# SOS_sender.net
KiCad netlist of a schematic drawn in EasyEDA
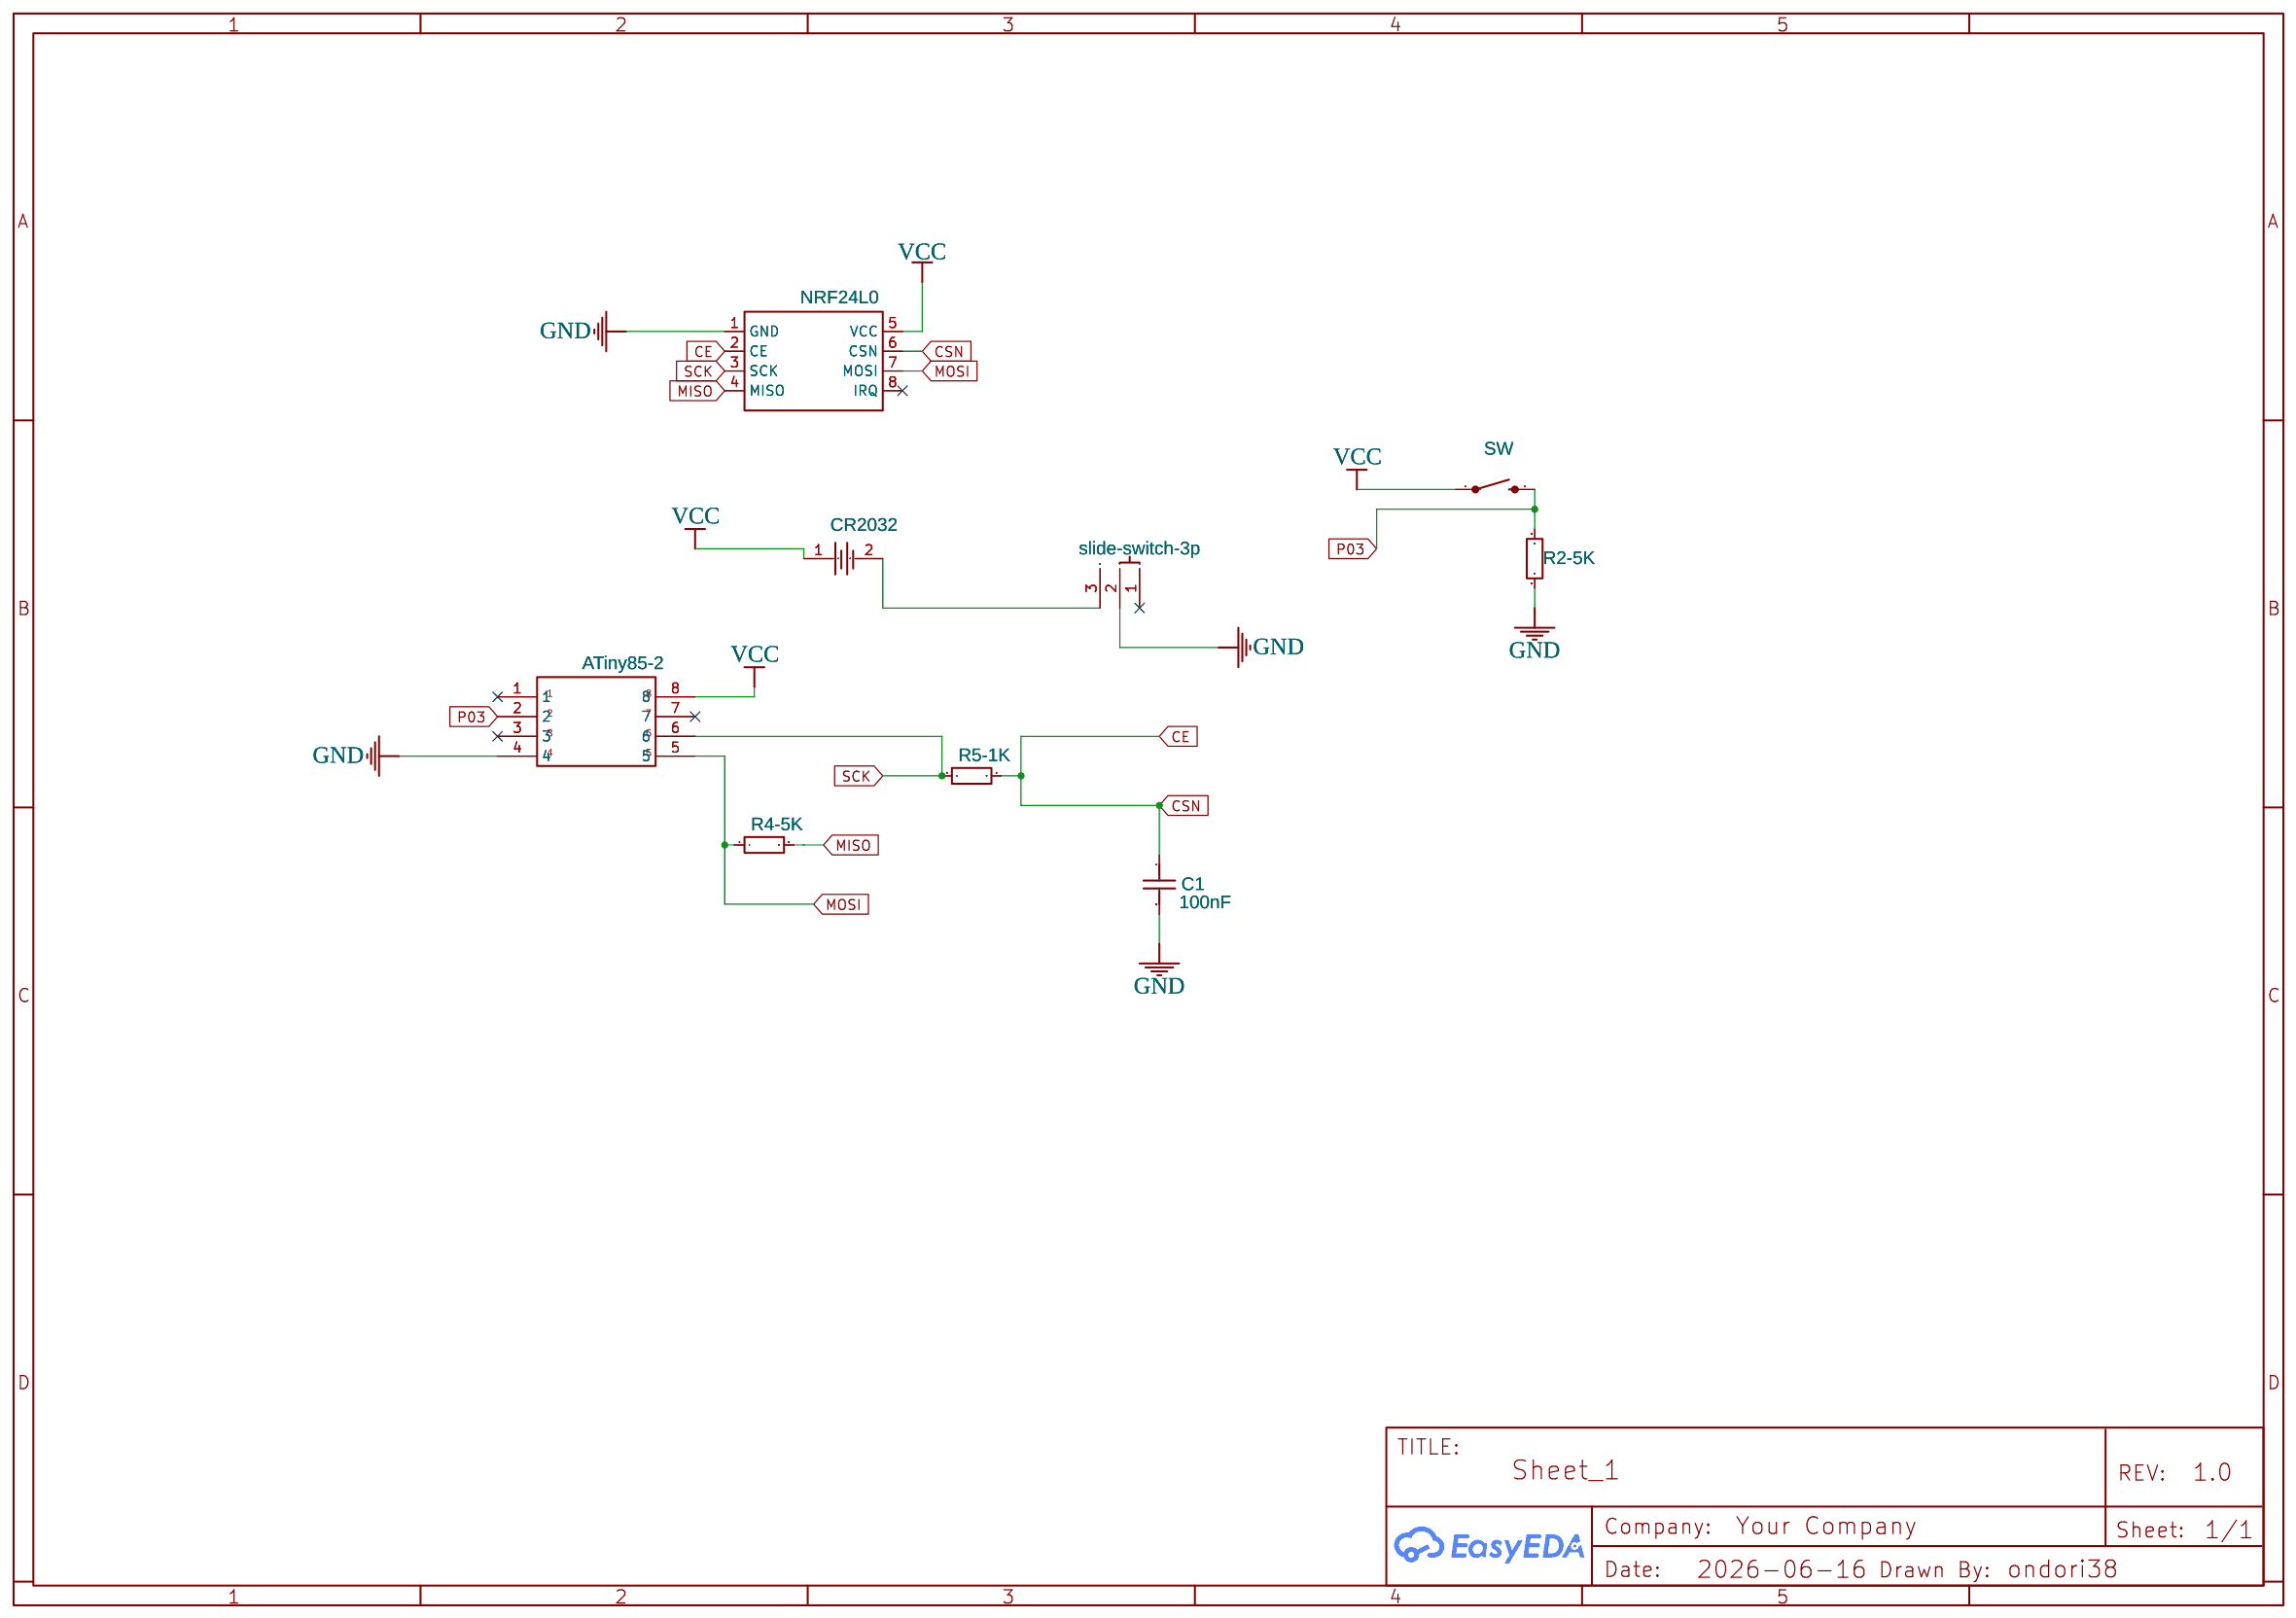
[diagram p0: schematic sheet]

(export (version "E")
  (design (tool "Eeschema 10.0.6"))
  (components
    (comp (ref "A1") (value "NRF24L0") (libsource (lib "") (part "NEF24L0")))
    (comp (ref "B1") (value "CR2032") (libsource (lib "") (part "BATT-CR2032")))
    (comp (ref "C1")
      (value "100nF")
      (fields (field (name "Manufacturer Part") "Capacitor-1206"))
      (libsource (lib "") (part "Capacitor SMD 1206"))
    )
    (comp (ref "R2")
      (value "R2-5K")
      (fields (field (name "Manufacturer Part") "C136529"))
      (libsource (lib "") (part "Resistor_THT_12,7mm_1"))
    )
    (comp (ref "R4")
      (value "R4-5K")
      (fields (field (name "Manufacturer Part") "C136529"))
      (libsource (lib "") (part "Resistor_THT_12,7mm"))
    )
    (comp (ref "R5")
      (value "R5-1K")
      (fields (field (name "Manufacturer Part") "C136529"))
      (libsource (lib "") (part "Resistor_THT_12,7mm"))
    )
    (comp (ref "SW") (value "SWITCHES_PTH_EZ") (libsource (lib "") (part "SWITCHES_PTH_EZ")))
    (comp (ref "SW2")
      (value "slide-switch-3p")
      (libsource (lib "") (part "slide-switch-3p-p3mm-handle-height"))
    )
    (comp (ref "U1") (value "ATiny85-2") (libsource (lib "") (part "ATiny85-2")))
  )
  (nets
    (net (code "1") (name "CE") (class "Default")
      (node (ref "A1") (pin "2") (pinfunction "CE_2") (pintype "unspecified"))
      (node (ref "A1") (pin "6") (pinfunction "CSN_6") (pintype "unspecified"))
      (node (ref "C1") (pin "1") (pinfunction "1_1") (pintype "unspecified"))
      (node (ref "R5") (pin "2") (pinfunction "2_2") (pintype "unspecified"))
    )
    (net (code "2") (name "GND") (class "Default")
      (node (ref "A1") (pin "1") (pinfunction "GND_1") (pintype "unspecified"))
      (node (ref "C1") (pin "2") (pinfunction "2_2") (pintype "unspecified"))
      (node (ref "R2") (pin "1") (pinfunction "1_1") (pintype "unspecified"))
      (node (ref "SW2") (pin "2") (pinfunction "COM_2") (pintype "unspecified"))
      (node (ref "U1") (pin "4") (pinfunction "4_4") (pintype "unspecified"))
    )
    (net (code "3") (name "MISO") (class "Default")
      (node (ref "A1") (pin "4") (pinfunction "MISO_4") (pintype "unspecified"))
      (node (ref "R4") (pin "2") (pinfunction "2_2") (pintype "unspecified"))
    )
    (net (code "4") (name "MOSI") (class "Default")
      (node (ref "A1") (pin "7") (pinfunction "MOSI_7") (pintype "unspecified"))
      (node (ref "R4") (pin "1") (pinfunction "1_1") (pintype "unspecified"))
      (node (ref "U1") (pin "5") (pinfunction "5_5") (pintype "unspecified"))
    )
    (net (code "5") (name "Net-(B1-Pad2)") (class "Default")
      (node (ref "B1") (pin "2") (pinfunction "2_2") (pintype "input"))
      (node (ref "SW2") (pin "3") (pinfunction "3_3") (pintype "unspecified"))
    )
    (net (code "6") (name "P03") (class "Default")
      (node (ref "R2") (pin "2") (pinfunction "2_2") (pintype "unspecified"))
      (node (ref "SW") (pin "3") (pinfunction "2_3") (pintype "unspecified"))
      (node (ref "U1") (pin "2") (pinfunction "2_2") (pintype "unspecified"))
    )
    (net (code "7") (name "SCK") (class "Default")
      (node (ref "A1") (pin "3") (pinfunction "SCK_3") (pintype "unspecified"))
      (node (ref "R5") (pin "1") (pinfunction "1_1") (pintype "unspecified"))
      (node (ref "U1") (pin "6") (pinfunction "6_6") (pintype "unspecified"))
    )
    (net (code "8") (name "VCC") (class "Default")
      (node (ref "A1") (pin "5") (pinfunction "VCC_5") (pintype "unspecified"))
      (node (ref "B1") (pin "1") (pinfunction "1_1") (pintype "input"))
      (node (ref "SW") (pin "1") (pinfunction "1_1") (pintype "unspecified"))
      (node (ref "U1") (pin "8") (pinfunction "8_8") (pintype "unspecified"))
    )
    (net (code "9") (name "unconnected-(A1-IRQ-Pad8)") (class "Default")
      (node (ref "A1") (pin "8") (pinfunction "IRQ_8") (pintype "unspecified+no_connect"))
    )
    (net (code "10") (name "unconnected-(SW2-Pad1)") (class "Default")
      (node (ref "SW2") (pin "1") (pinfunction "1_1") (pintype "unspecified+no_connect"))
    )
    (net (code "11") (name "unconnected-(U1-Pad1)") (class "Default")
      (node (ref "U1") (pin "1") (pinfunction "1_1") (pintype "unspecified+no_connect"))
    )
    (net (code "12") (name "unconnected-(U1-Pad3)") (class "Default")
      (node (ref "U1") (pin "3") (pinfunction "3_3") (pintype "unspecified+no_connect"))
    )
    (net (code "13") (name "unconnected-(U1-Pad7)") (class "Default")
      (node (ref "U1") (pin "7") (pinfunction "7_7") (pintype "unspecified+no_connect"))
    )
  )
)
